# USBm1P_0v0.net
KiCad netlist of a schematic drawn in EAGLE
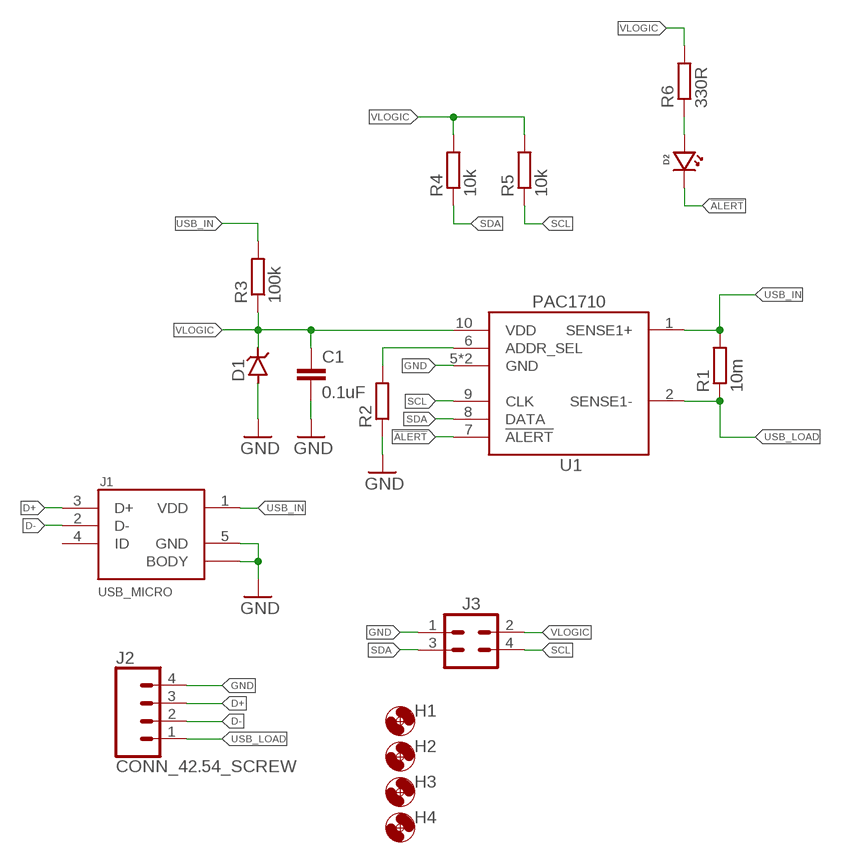
[diagram p0: schematic, sheet 1]

(export (version "E")
  (design (tool "Eeschema 10.0.6"))
  (components
    (comp (ref "C1")
      (value "0.1uF")
      (footprint "eagle-import:C0603")
      (fields (field (name "MF") "Murata") (field (name "MPN") "GCM188R71E104KA57D"))
      (libsource (lib "eagle-import") (part "C-EUC06030.1UF"))
    )
    (comp (ref "D1")
      (value "DIODE_ZENERSOD-123")
      (footprint "eagle-import:SOD-123")
      (libsource (lib "eagle-import") (part "DIODE_ZENERSOD-123"))
    )
    (comp (ref "D2")
      (value "LED1206_BOTTOM")
      (footprint "eagle-import:LED_1206_BOTTOM")
      (libsource (lib "eagle-import") (part "LED1206_BOTTOM"))
    )
    (comp (ref "H1")
      (value "MOUNTING_HOLE2_NP")
      (footprint "eagle-import:2_56")
      (fields (field (name "MPN") "DNP"))
      (libsource (lib "eagle-import") (part "MOUNTING_HOLE2_NP"))
    )
    (comp (ref "H2")
      (value "MOUNTING_HOLE2_NP")
      (footprint "eagle-import:2_56")
      (fields (field (name "MPN") "DNP"))
      (libsource (lib "eagle-import") (part "MOUNTING_HOLE2_NP"))
    )
    (comp (ref "H3")
      (value "MOUNTING_HOLE2_NP")
      (footprint "eagle-import:2_56")
      (fields (field (name "MPN") "DNP"))
      (libsource (lib "eagle-import") (part "MOUNTING_HOLE2_NP"))
    )
    (comp (ref "H4")
      (value "MOUNTING_HOLE2_NP")
      (footprint "eagle-import:2_56")
      (fields (field (name "MPN") "DNP"))
      (libsource (lib "eagle-import") (part "MOUNTING_HOLE2_NP"))
    )
    (comp (ref "J1")
      (value "USB_MICRO")
      (footprint "eagle-import:10118194-0001LF_10118194-0001LF_LONGER_PADS")
      (fields (field (name "MF") "Amphenol") (field (name "MPN") "10118194-0001LF"))
      (libsource (lib "eagle-import") (part "USB_MICRO"))
    )
    (comp (ref "J2")
      (value "CONN_42.54_SCREW")
      (footprint "eagle-import:1X04_SCREW")
      (fields (field (name "MF") "On Shore") (field (name "MPN") "OSTVN04A150"))
      (libsource (lib "eagle-import") (part "CONN_42.54_SCREW"))
    )
    (comp (ref "J3")
      (value "CONN_2X2MIRCOFIT_RT")
      (footprint "eagle-import:2X2_MICROFIT_RT")
      (fields (field (name "MF") "Molex") (field (name "MPN") "0430450400"))
      (libsource (lib "eagle-import") (part "CONN_2X2MIRCOFIT_RT"))
    )
    (comp (ref "R1")
      (value "10m")
      (footprint "eagle-import:R0805")
      (fields (field (name "MF") "Bourns") (field (name "MPN") "CRF0805-FZ-R010ELF"))
      (libsource (lib "eagle-import") (part "R-EU_R08050.01"))
    )
    (comp (ref "R2")
      (value "R-EU_R0603")
      (footprint "eagle-import:R0603")
      (fields (field (name "MF") "Yageo"))
      (libsource (lib "eagle-import") (part "R-EU_R0603"))
    )
    (comp (ref "R3")
      (value "100k")
      (footprint "eagle-import:R0603")
      (fields (field (name "MF") "Yageo") (field (name "MPN") "RC0603FR-07100KL"))
      (libsource (lib "eagle-import") (part "R-EU_R0603100K"))
    )
    (comp (ref "R4")
      (value "10k")
      (footprint "eagle-import:R0603")
      (fields (field (name "MF") "Yageo") (field (name "MPN") "RC0603FR-0710KL"))
      (libsource (lib "eagle-import") (part "R-EU_R060310K"))
    )
    (comp (ref "R5")
      (value "10k")
      (footprint "eagle-import:R0603")
      (fields (field (name "MF") "Yageo") (field (name "MPN") "RC0603FR-0710KL"))
      (libsource (lib "eagle-import") (part "R-EU_R060310K"))
    )
    (comp (ref "R6")
      (value "330R")
      (footprint "eagle-import:R0603")
      (fields
        (field (name "MF") "Yageo")
        (field (name "MPN") "RC0603FR-07330RL")
        (field (name "VALUE_PART") "330")
      )
      (libsource (lib "eagle-import") (part "R-EU_R0603330"))
    )
    (comp (ref "U1")
      (value "PAC1710")
      (footprint "eagle-import:VDFN-10")
      (fields (field (name "MF") "Microchip") (field (name "MPN") "PAC1710-1-AIA-TR"))
      (libsource (lib "eagle-import") (part "PAC1710"))
    )
  )
  (nets
    (net (code "1") (name "/~{ALERT}") (class "Default")
      (node (ref "D2") (pin "CATHODE") (pinfunction "CATHODE_CATHODE") (pintype "power_in"))
      (node (ref "U1") (pin "7") (pinfunction "~{ALERT}_7") (pintype "output"))
    )
    (net (code "2") (name "D+") (class "Default")
      (node (ref "J1") (pin "3") (pinfunction "D+_3") (pintype "bidirectional"))
      (node (ref "J2") (pin "3") (pinfunction "3_3") (pintype "passive"))
    )
    (net (code "3") (name "D-") (class "Default")
      (node (ref "J1") (pin "2") (pinfunction "D-_2") (pintype "bidirectional"))
      (node (ref "J2") (pin "2") (pinfunction "2_2") (pintype "passive"))
    )
    (net (code "4") (name "GND") (class "Default")
      (node (ref "C1") (pin "2") (pinfunction "2_2") (pintype "passive"))
      (node (ref "D1") (pin "ANODE") (pinfunction "A_ANODE") (pintype "passive"))
      (node (ref "J1") (pin "5") (pinfunction "GND_5") (pintype "power_in"))
      (node (ref "J1") (pin "BODY@1") (pinfunction "BODY_BODY@1") (pintype "bidirectional"))
      (node (ref "J1") (pin "BODY@2") (pinfunction "BODY_BODY@2") (pintype "bidirectional"))
      (node (ref "J1") (pin "BODY@3") (pinfunction "BODY_BODY@3") (pintype "bidirectional"))
      (node (ref "J1") (pin "BODY@4") (pinfunction "BODY_BODY@4") (pintype "bidirectional"))
      (node (ref "J1") (pin "BODY@7") (pinfunction "BODY_BODY@7") (pintype "bidirectional"))
      (node (ref "J1") (pin "BODY@8") (pinfunction "BODY_BODY@8") (pintype "bidirectional"))
      (node (ref "J2") (pin "4") (pinfunction "4_4") (pintype "passive"))
      (node (ref "J3") (pin "1") (pinfunction "1_1") (pintype "bidirectional"))
      (node (ref "R2") (pin "1") (pinfunction "1_1") (pintype "passive"))
      (node (ref "U1") (pin "5") (pinfunction "GND_5") (pintype "power_in"))
      (node (ref "U1") (pin "EP") (pinfunction "GND_EP") (pintype "power_in"))
    )
    (net (code "5") (name "Net-(D2-PadANODE)") (class "Default")
      (node (ref "D2") (pin "ANODE") (pinfunction "ANODE_ANODE") (pintype "power_in"))
      (node (ref "R6") (pin "1") (pinfunction "1_1") (pintype "passive"))
    )
    (net (code "6") (name "Net-(U1-ADDR_SEL)") (class "Default")
      (node (ref "R2") (pin "2") (pinfunction "2_2") (pintype "passive"))
      (node (ref "U1") (pin "6") (pinfunction "ADDR_SEL_6") (pintype "input"))
    )
    (net (code "7") (name "SCL") (class "Default")
      (node (ref "J3") (pin "4") (pinfunction "4_4") (pintype "bidirectional"))
      (node (ref "R5") (pin "1") (pinfunction "1_1") (pintype "passive"))
      (node (ref "U1") (pin "9") (pinfunction "CLK_9") (pintype "input"))
    )
    (net (code "8") (name "SDA") (class "Default")
      (node (ref "J3") (pin "3") (pinfunction "3_3") (pintype "bidirectional"))
      (node (ref "R4") (pin "1") (pinfunction "1_1") (pintype "passive"))
      (node (ref "U1") (pin "8") (pinfunction "DATA_8") (pintype "bidirectional"))
    )
    (net (code "9") (name "USB_IN") (class "Default")
      (node (ref "J1") (pin "1") (pinfunction "VDD_1") (pintype "power_in"))
      (node (ref "R1") (pin "2") (pinfunction "2_2") (pintype "passive"))
      (node (ref "R3") (pin "2") (pinfunction "2_2") (pintype "passive"))
      (node (ref "U1") (pin "1") (pinfunction "SENSE1+_1") (pintype "input"))
    )
    (net (code "10") (name "USB_LOAD") (class "Default")
      (node (ref "J2") (pin "1") (pinfunction "1_1") (pintype "passive"))
      (node (ref "R1") (pin "1") (pinfunction "1_1") (pintype "passive"))
      (node (ref "U1") (pin "2") (pinfunction "SENSE1-_2") (pintype "input"))
    )
    (net (code "11") (name "VLOGIC") (class "Default")
      (node (ref "C1") (pin "1") (pinfunction "1_1") (pintype "passive"))
      (node (ref "D1") (pin "CAT") (pinfunction "C_CAT") (pintype "passive"))
      (node (ref "J3") (pin "2") (pinfunction "2_2") (pintype "bidirectional"))
      (node (ref "R3") (pin "1") (pinfunction "1_1") (pintype "passive"))
      (node (ref "R4") (pin "2") (pinfunction "2_2") (pintype "passive"))
      (node (ref "R5") (pin "2") (pinfunction "2_2") (pintype "passive"))
      (node (ref "R6") (pin "2") (pinfunction "2_2") (pintype "passive"))
      (node (ref "U1") (pin "10") (pinfunction "VDD_10") (pintype "power_in"))
    )
    (net (code "12") (name "unconnected-(J1-ID-Pad4)") (class "Default")
      (node (ref "J1") (pin "4") (pinfunction "ID_4") (pintype "passive"))
    )
  )
)
